# Connector_Board_rev2.net
KiCad netlist of a schematic drawn in EAGLE
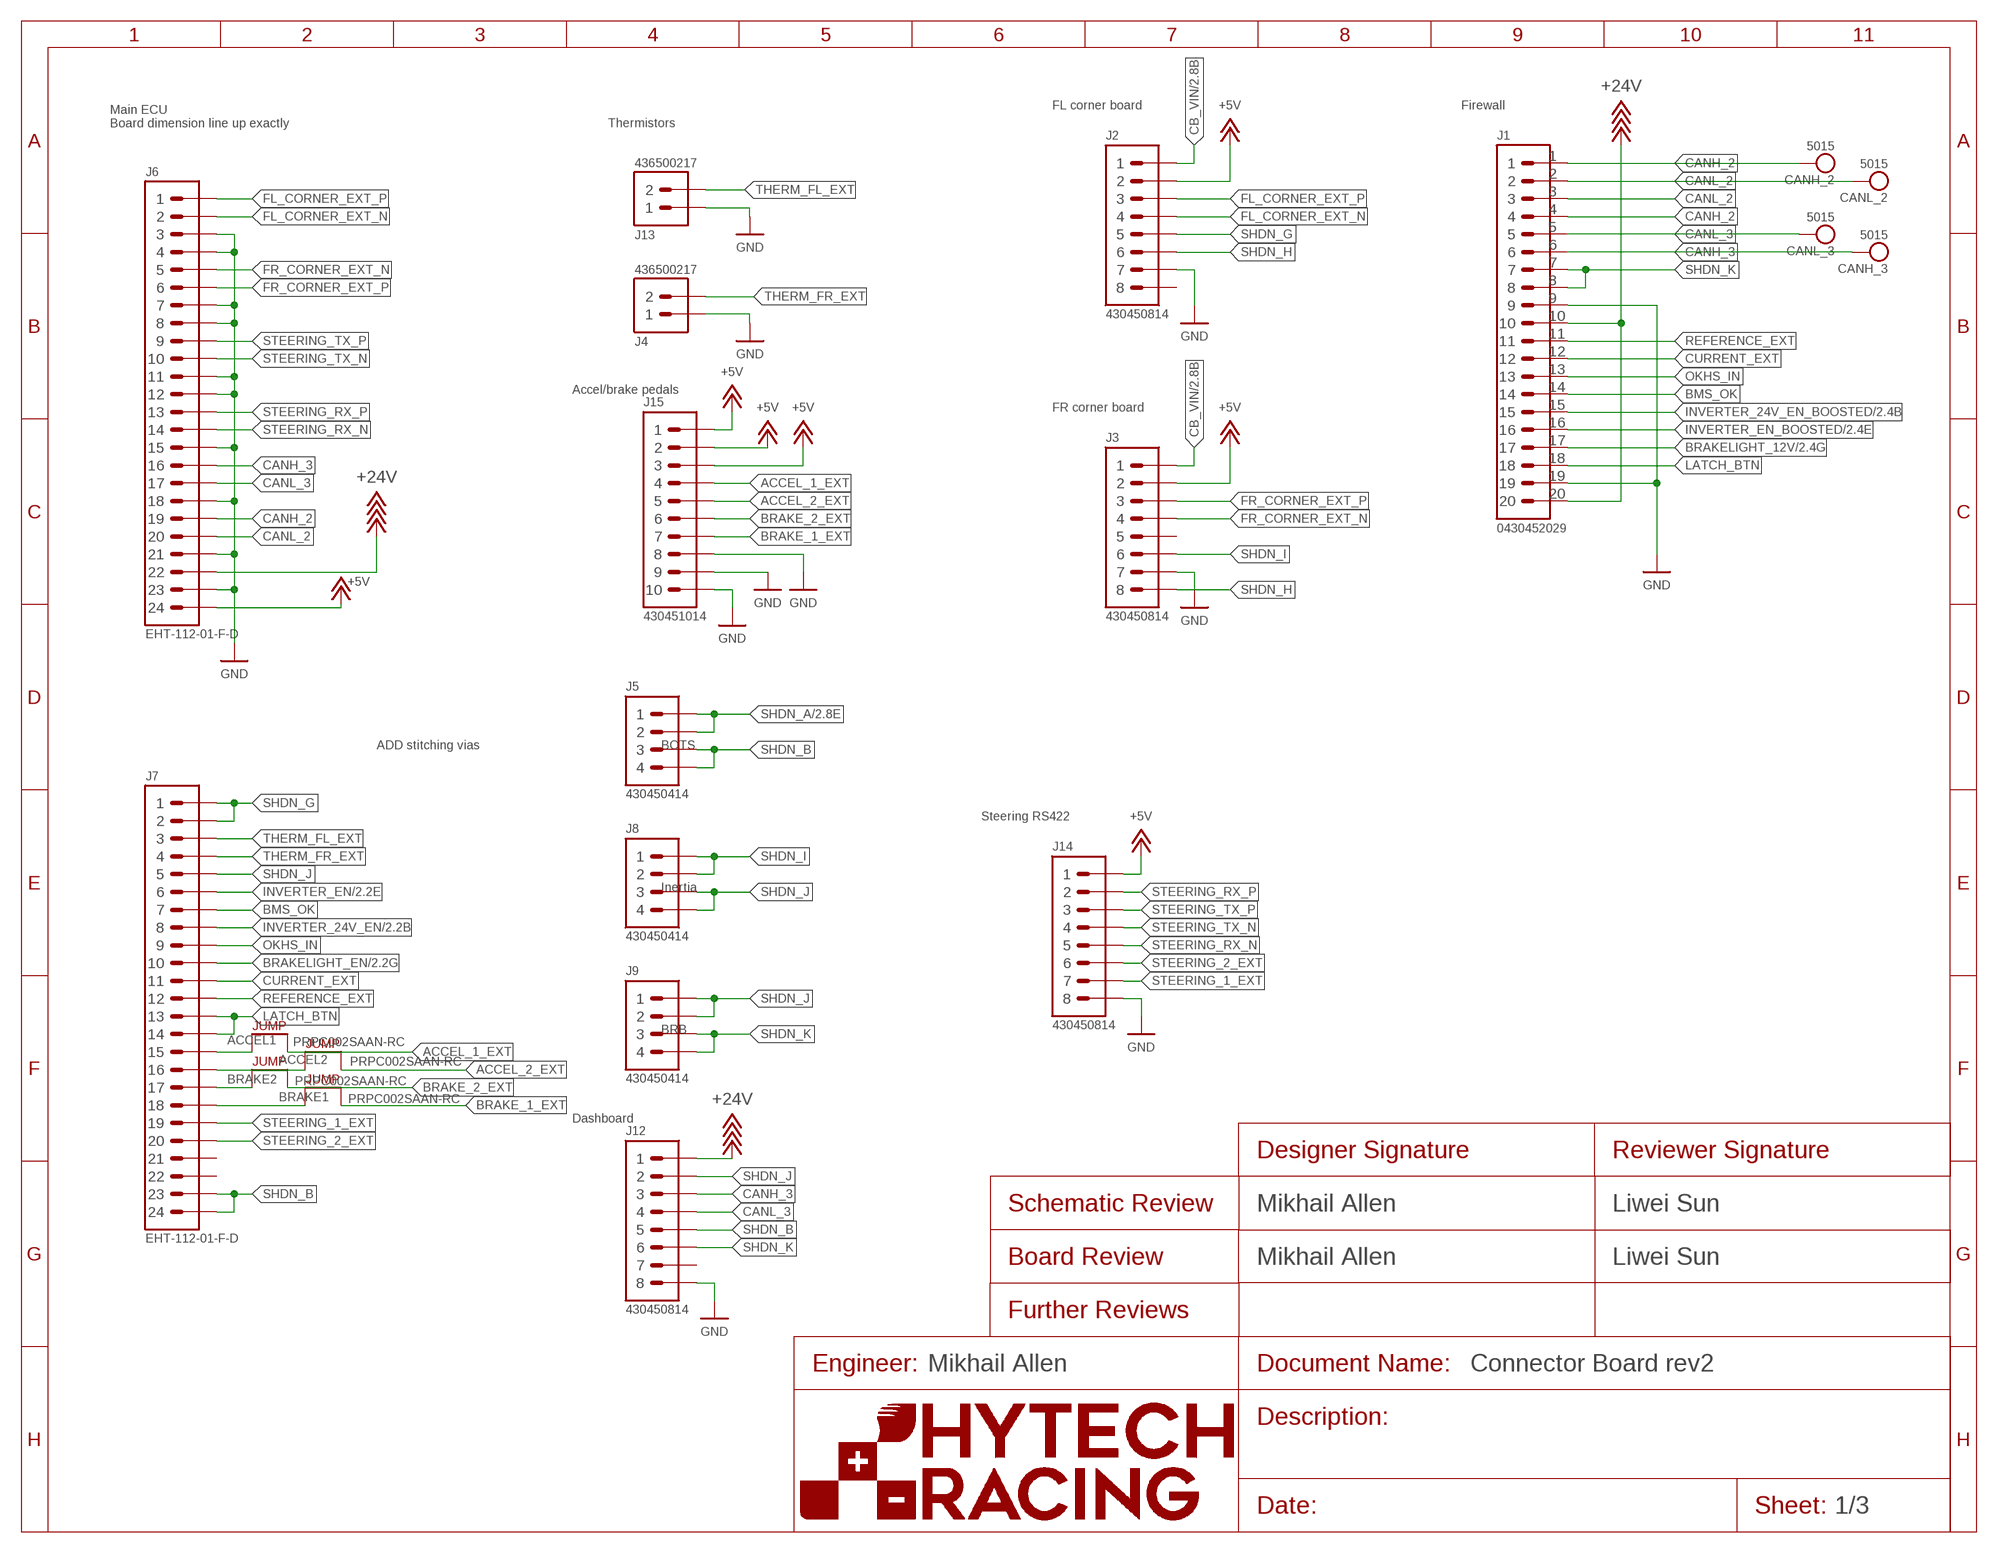
[diagram p0: schematic, sheet 1]
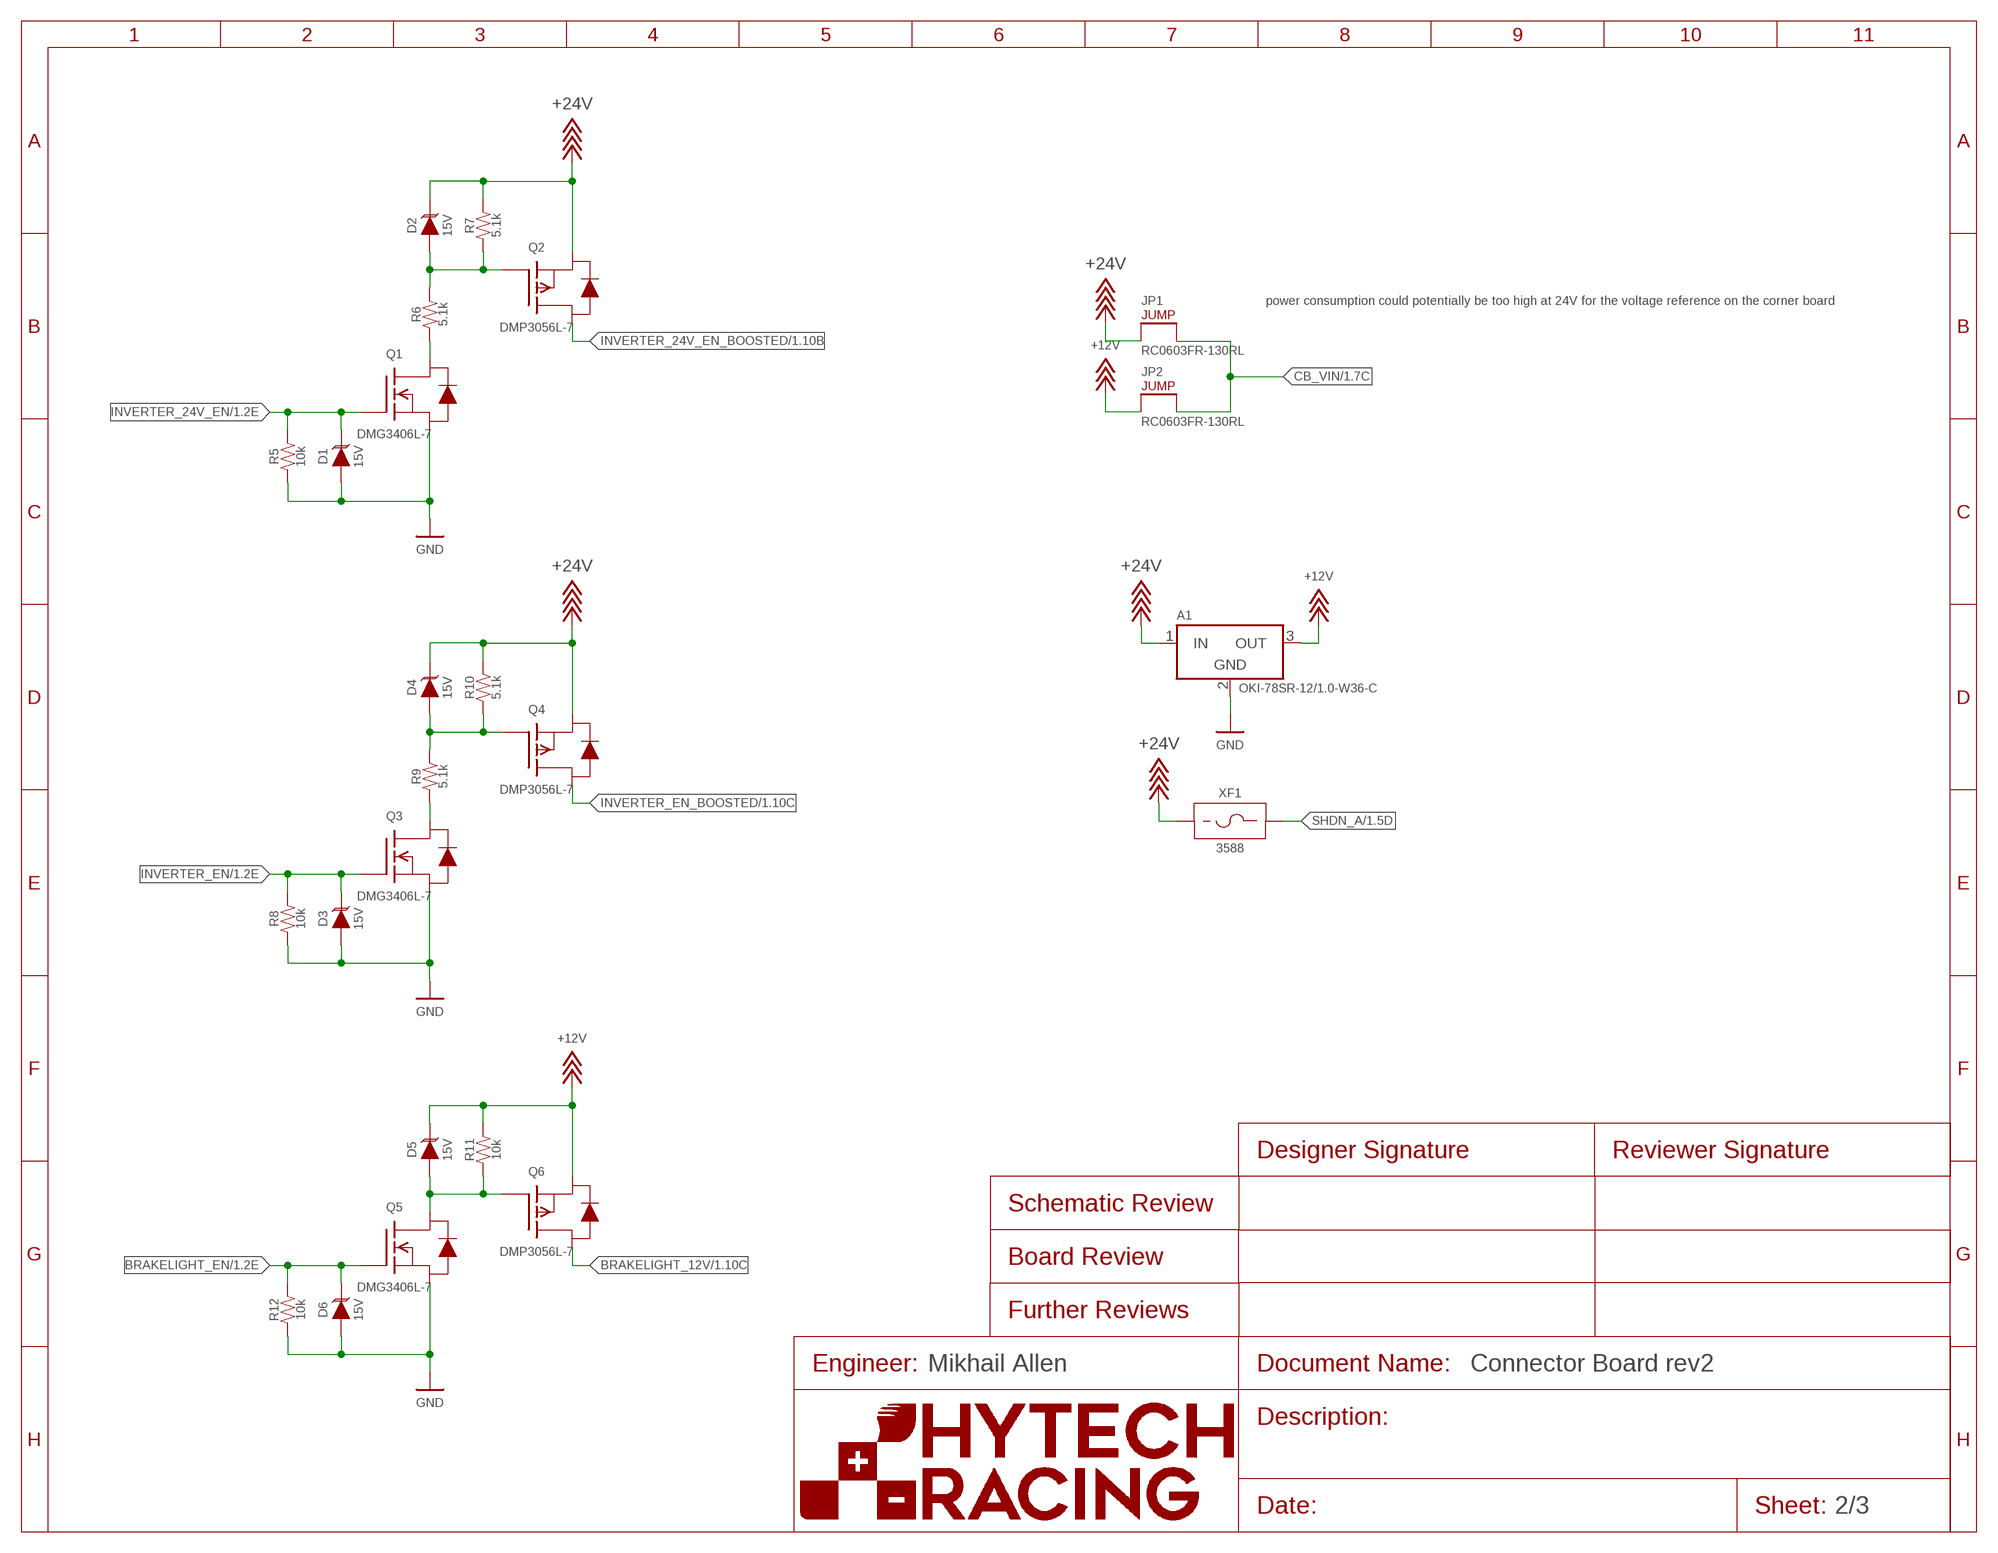
[diagram p1: schematic, sheet 2]
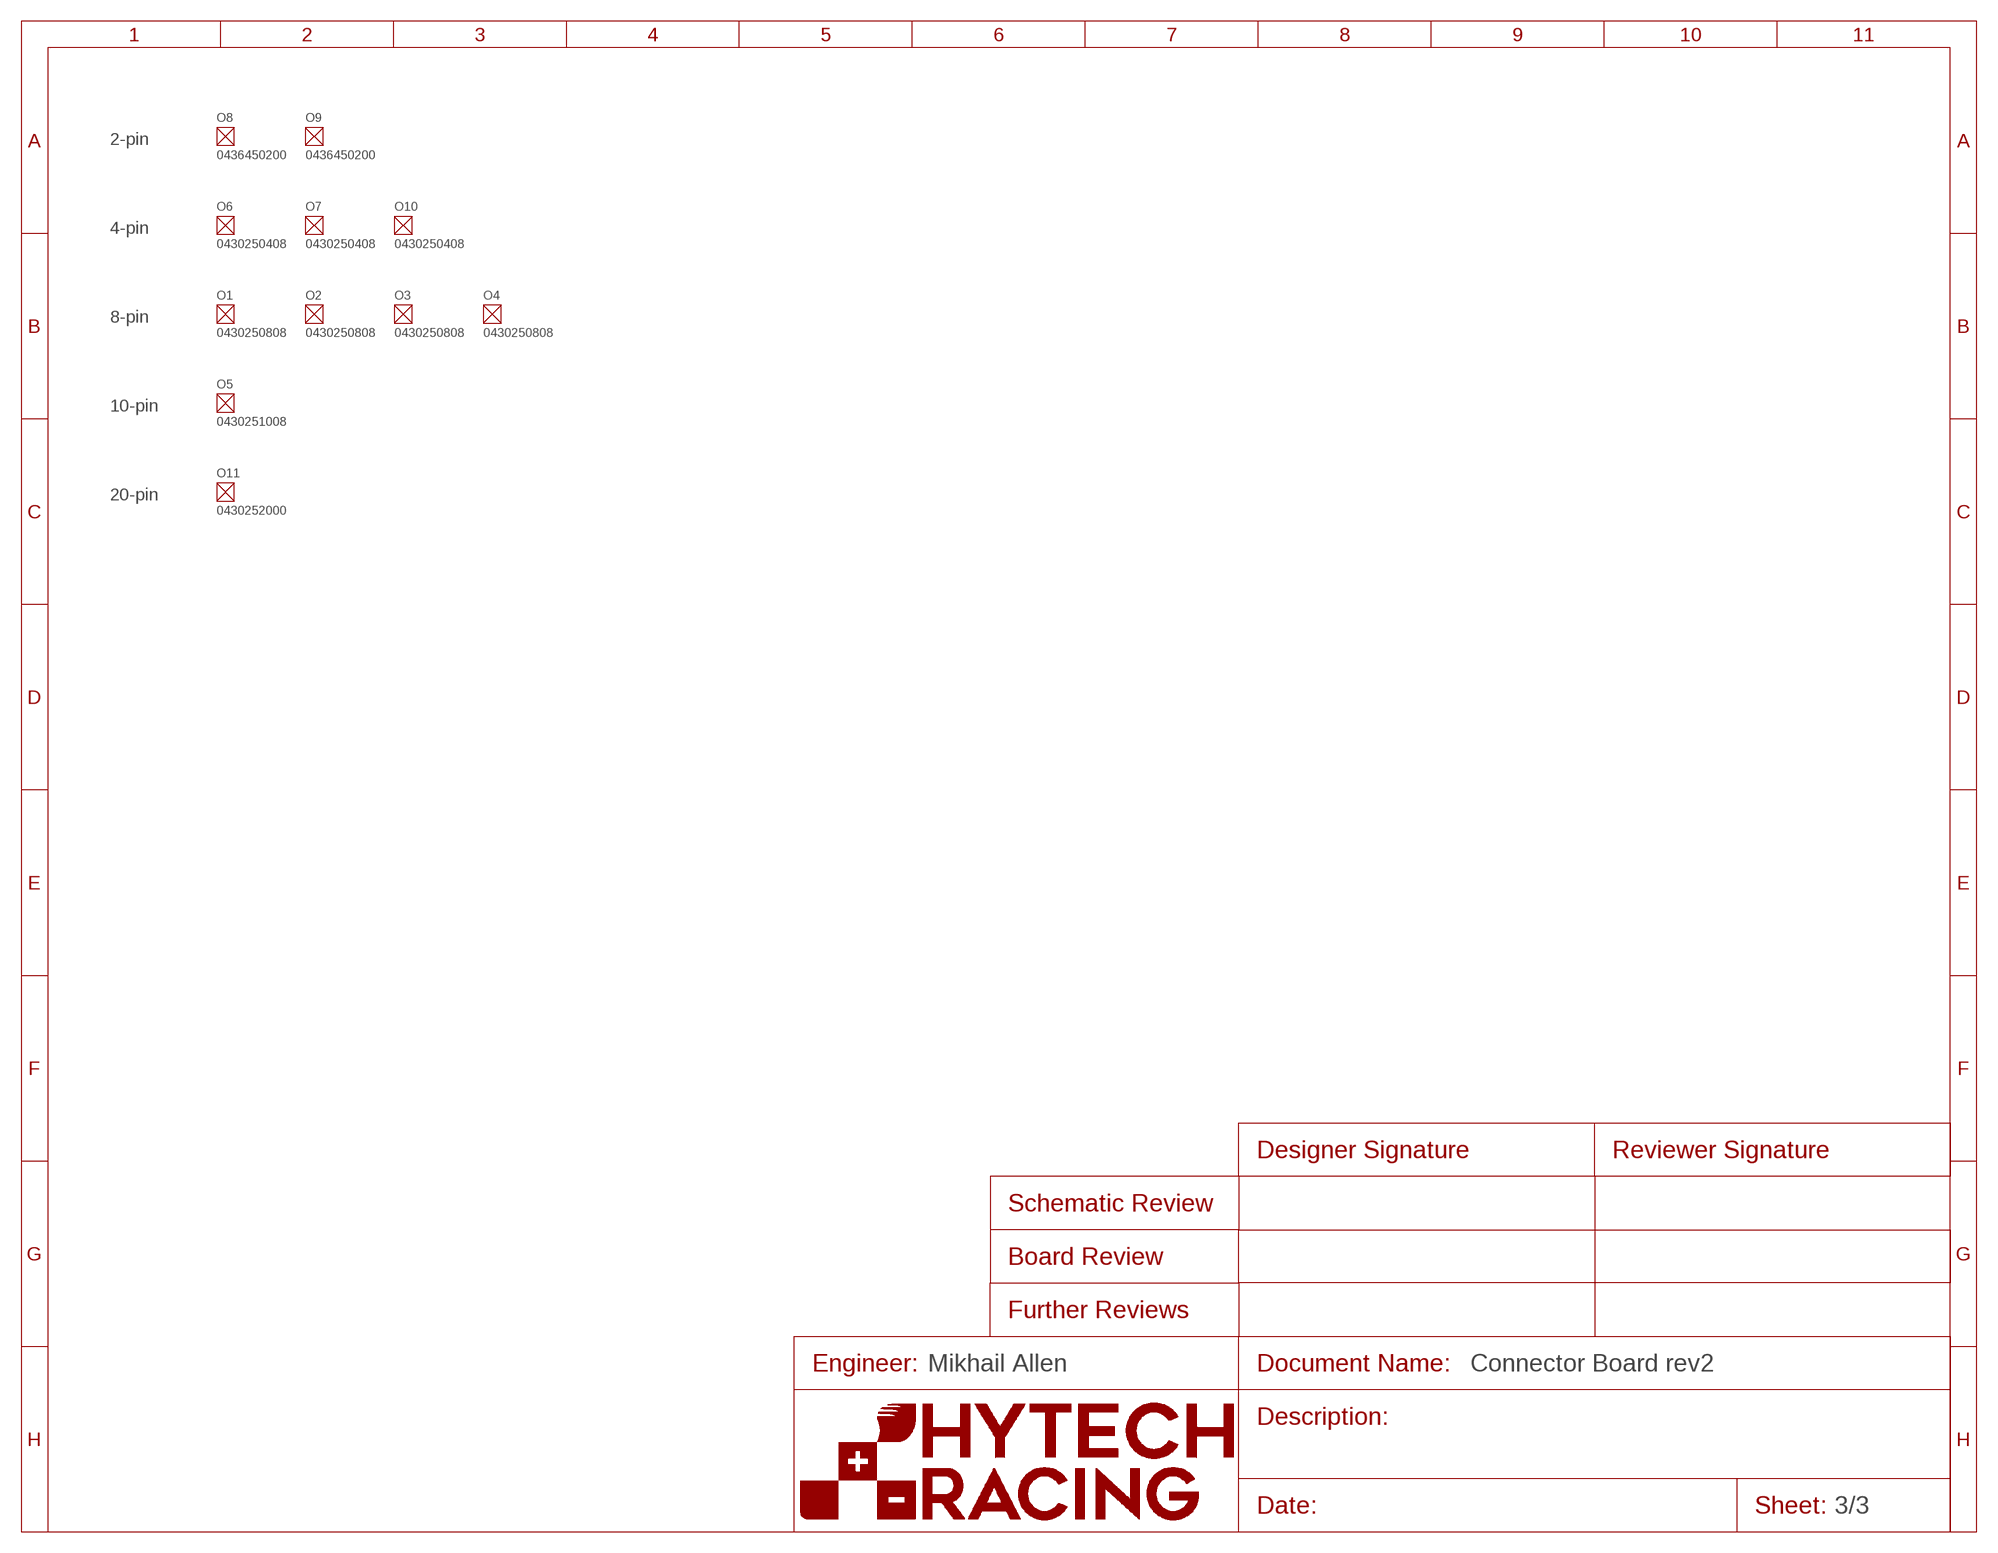
[diagram p2: schematic, sheet 3]

(export (version "E")
  (design (tool "Eeschema 10.0.6"))
  (components
    (comp (ref "ACCEL1")
      (value "JUMPER__1X02")
      (footprint "eagle-import:1X02")
      (fields
        (field (name "MANUFACTURER") "Sullins Connector Solutions")
        (field (name "MPN") "PRPC002SAAN-RC")
      )
      (libsource (lib "eagle-import") (part "JUMPER_?_1X02"))
    )
    (comp (ref "ACCEL2")
      (value "JUMPER__1X02")
      (footprint "eagle-import:1X02")
      (fields
        (field (name "MANUFACTURER") "Sullins Connector Solutions")
        (field (name "MPN") "PRPC002SAAN-RC")
      )
      (libsource (lib "eagle-import") (part "JUMPER_?_1X02"))
    )
    (comp (ref "BRAKE1")
      (value "JUMPER__1X02")
      (footprint "eagle-import:1X02")
      (fields
        (field (name "MANUFACTURER") "Sullins Connector Solutions")
        (field (name "MPN") "PRPC002SAAN-RC")
      )
      (libsource (lib "eagle-import") (part "JUMPER_?_1X02"))
    )
    (comp (ref "BRAKE2")
      (value "JUMPER__1X02")
      (footprint "eagle-import:1X02")
      (fields
        (field (name "MANUFACTURER") "Sullins Connector Solutions")
        (field (name "MPN") "PRPC002SAAN-RC")
      )
      (libsource (lib "eagle-import") (part "JUMPER_?_1X02"))
    )
    (comp (ref "CANH_2")
      (value "TEST_POINT")
      (footprint "eagle-import:5015")
      (fields (field (name "MPN") "5015") (field (name "MANUFACTURER") "Keystone Electronics"))
      (libsource (lib "eagle-import") (part "TEST_POINT"))
    )
    (comp (ref "CANH_3")
      (value "TEST_POINT")
      (footprint "eagle-import:5015")
      (fields (field (name "MPN") "5015") (field (name "MANUFACTURER") "Keystone Electronics"))
      (libsource (lib "eagle-import") (part "TEST_POINT"))
    )
    (comp (ref "CANL_2")
      (value "TEST_POINT")
      (footprint "eagle-import:5015")
      (fields (field (name "MPN") "5015") (field (name "MANUFACTURER") "Keystone Electronics"))
      (libsource (lib "eagle-import") (part "TEST_POINT"))
    )
    (comp (ref "CANL_3")
      (value "TEST_POINT")
      (footprint "eagle-import:5015")
      (fields (field (name "MPN") "5015") (field (name "MANUFACTURER") "Keystone Electronics"))
      (libsource (lib "eagle-import") (part "TEST_POINT"))
    )
    (comp (ref "J1")
      (value "CONNECTOR-20_MF_T_V_")
      (footprint "eagle-import:MOLEX_MICROFIT_PTH_VERTICAL_20_DUAL")
      (fields (field (name "MPN") "0430452029") (field (name "MANUFACTURER") "Molex"))
      (libsource (lib "eagle-import") (part "CONNECTOR-20_?_MF_T_V"))
    )
    (comp (ref "J2")
      (value "CONNECTOR-8_μF_T_V_BLACK")
      (footprint "eagle-import:MOLEX_MICROFIT_PTH_VERTICAL_08_DUAL")
      (fields (field (name "MANUFACTURER") "Molex") (field (name "MPN") "430450814"))
      (libsource (lib "eagle-import") (part "CONNECTOR-8_?_μF_T_VBLACK"))
    )
    (comp (ref "J3")
      (value "CONNECTOR-8_μF_T_V_BLACK")
      (footprint "eagle-import:MOLEX_MICROFIT_PTH_VERTICAL_08_DUAL")
      (fields (field (name "MANUFACTURER") "Molex") (field (name "MPN") "430450814"))
      (libsource (lib "eagle-import") (part "CONNECTOR-8_?_μF_T_VBLACK"))
    )
    (comp (ref "J4")
      (value "CONNECTOR-2_MF_T_V_")
      (footprint "eagle-import:MOLEX_MICROFIT_PTH_VERTICAL_02_SINGLE")
      (fields (field (name "MPN") "436500217") (field (name "MANUFACTURER") "MOLEX"))
      (libsource (lib "eagle-import") (part "CONNECTOR-2_?_MF_T_V"))
    )
    (comp (ref "J5")
      (value "CONNECTOR-4_μF_T_V_BLACK")
      (footprint "eagle-import:MOLEX_MICROFIT_PTH_VERTICAL_04_DUAL")
      (fields (field (name "MANUFACTURER") "Molex") (field (name "MPN") "430450414"))
      (libsource (lib "eagle-import") (part "CONNECTOR-4_?_μF_T_VBLACK"))
    )
    (comp (ref "J6")
      (value "CONNECTOR-24_CONNECTOR-24_")
      (footprint "eagle-import:EHT-112-01")
      (fields (field (name "MPN") "EHT-112-01-F-D") (field (name "MANUFACTURER") "Samtec"))
      (libsource (lib "eagle-import") (part "CONNECTOR-24_?_CONNECTOR-24"))
    )
    (comp (ref "J7")
      (value "CONNECTOR-24_CONNECTOR-24_")
      (footprint "eagle-import:EHT-112-01")
      (fields (field (name "MPN") "EHT-112-01-F-D") (field (name "MANUFACTURER") "Samtec"))
      (libsource (lib "eagle-import") (part "CONNECTOR-24_?_CONNECTOR-24"))
    )
    (comp (ref "J8")
      (value "CONNECTOR-4_μF_T_V_BLACK")
      (footprint "eagle-import:MOLEX_MICROFIT_PTH_VERTICAL_04_DUAL")
      (fields (field (name "MANUFACTURER") "Molex") (field (name "MPN") "430450414"))
      (libsource (lib "eagle-import") (part "CONNECTOR-4_?_μF_T_VBLACK"))
    )
    (comp (ref "J9")
      (value "CONNECTOR-4_μF_T_V_BLACK")
      (footprint "eagle-import:MOLEX_MICROFIT_PTH_VERTICAL_04_DUAL")
      (fields (field (name "MANUFACTURER") "Molex") (field (name "MPN") "430450414"))
      (libsource (lib "eagle-import") (part "CONNECTOR-4_?_μF_T_VBLACK"))
    )
    (comp (ref "J12")
      (value "CONNECTOR-8_μF_T_V_BLACK")
      (footprint "eagle-import:MOLEX_MICROFIT_PTH_VERTICAL_08_DUAL")
      (fields (field (name "MANUFACTURER") "Molex") (field (name "MPN") "430450814"))
      (libsource (lib "eagle-import") (part "CONNECTOR-8_?_μF_T_VBLACK"))
    )
    (comp (ref "J13")
      (value "CONNECTOR-2_MF_T_V_")
      (footprint "eagle-import:MOLEX_MICROFIT_PTH_VERTICAL_02_SINGLE")
      (fields (field (name "MPN") "436500217") (field (name "MANUFACTURER") "MOLEX"))
      (libsource (lib "eagle-import") (part "CONNECTOR-2_?_MF_T_V"))
    )
    (comp (ref "J14")
      (value "CONNECTOR-8_μF_T_V_BLACK")
      (footprint "eagle-import:MOLEX_MICROFIT_PTH_VERTICAL_08_DUAL")
      (fields (field (name "MANUFACTURER") "Molex") (field (name "MPN") "430450814"))
      (libsource (lib "eagle-import") (part "CONNECTOR-8_?_μF_T_VBLACK"))
    )
    (comp (ref "J15")
      (value "CONNECTOR-10_MF_T_V_")
      (footprint "eagle-import:MOLEX_MICROFIT_PTH_VERTICAL_10_DUAL")
      (fields (field (name "MPN") "430451014") (field (name "MANUFACTURER") "MOLEX"))
      (libsource (lib "eagle-import") (part "CONNECTOR-10_?_MF_T_V"))
    )
    (comp (ref "A1")
      (value "VOLTAGE_REGULATOR_MODULE_OKI-78SR_12V")
      (footprint "eagle-import:OKI-78SR")
      (fields
        (field (name "MANUFACTURER") "Murata Power Solutions Inc.")
        (field (name "MPN") "OKI-78SR-12/1.0-W36-C")
      )
      (libsource (lib "eagle-import") (part "VOLTAGE_REGULATOR_MODULE_?_OKI-78SR12V"))
    )
    (comp (ref "D1")
      (value "TVS__15V")
      (footprint "eagle-import:SOT-23")
      (fields
        (field (name "MANUFACTURER") "Vishay General Semiconductor - Diodes Division")
        (field (name "MPN") "GSOT15-E3-08")
        (field (name "VOLTAGE") "15V")
      )
      (libsource (lib "eagle-import") (part "TVS_?_15V"))
    )
    (comp (ref "D2")
      (value "TVS__15V")
      (footprint "eagle-import:SOT-23")
      (fields
        (field (name "MANUFACTURER") "Vishay General Semiconductor - Diodes Division")
        (field (name "MPN") "GSOT15-E3-08")
        (field (name "VOLTAGE") "15V")
      )
      (libsource (lib "eagle-import") (part "TVS_?_15V"))
    )
    (comp (ref "D3")
      (value "TVS__15V")
      (footprint "eagle-import:SOT-23")
      (fields
        (field (name "MANUFACTURER") "Vishay General Semiconductor - Diodes Division")
        (field (name "MPN") "GSOT15-E3-08")
        (field (name "VOLTAGE") "15V")
      )
      (libsource (lib "eagle-import") (part "TVS_?_15V"))
    )
    (comp (ref "D4")
      (value "TVS__15V")
      (footprint "eagle-import:SOT-23")
      (fields
        (field (name "MANUFACTURER") "Vishay General Semiconductor - Diodes Division")
        (field (name "MPN") "GSOT15-E3-08")
        (field (name "VOLTAGE") "15V")
      )
      (libsource (lib "eagle-import") (part "TVS_?_15V"))
    )
    (comp (ref "D5")
      (value "TVS__15V")
      (footprint "eagle-import:SOT-23")
      (fields
        (field (name "MANUFACTURER") "Vishay General Semiconductor - Diodes Division")
        (field (name "MPN") "GSOT15-E3-08")
        (field (name "VOLTAGE") "15V")
      )
      (libsource (lib "eagle-import") (part "TVS_?_15V"))
    )
    (comp (ref "D6")
      (value "TVS__15V")
      (footprint "eagle-import:SOT-23")
      (fields
        (field (name "MANUFACTURER") "Vishay General Semiconductor - Diodes Division")
        (field (name "MPN") "GSOT15-E3-08")
        (field (name "VOLTAGE") "15V")
      )
      (libsource (lib "eagle-import") (part "TVS_?_15V"))
    )
    (comp (ref "JP1")
      (value "JUMPER_0603_")
      (footprint "eagle-import:0603-RES")
      (fields (field (name "MPN") "RC0603FR-130RL") (field (name "MANUFACTURER") "YAGEO"))
      (libsource (lib "eagle-import") (part "JUMPER_?_0603"))
    )
    (comp (ref "JP2")
      (value "JUMPER_0603_")
      (footprint "eagle-import:0603-RES")
      (fields (field (name "MPN") "RC0603FR-130RL") (field (name "MANUFACTURER") "YAGEO"))
      (libsource (lib "eagle-import") (part "JUMPER_?_0603"))
    )
    (comp (ref "Q1")
      (value "TRANSISTOR_N_MOS__DMG3406L-7")
      (footprint "eagle-import:SOT-23")
      (fields (field (name "MANUFACTURER") "Diodes Incorporated") (field (name "MPN") "DMG3406L-7"))
      (libsource (lib "eagle-import") (part "TRANSISTOR_N_MOS_?_DMG3406L-7"))
    )
    (comp (ref "Q2")
      (value "TRANSISTOR_P_MOS_SOT-23_DMP3056L-7")
      (footprint "eagle-import:SOT-23")
      (fields (field (name "MANUFACTURER") "Diodes Incorporated") (field (name "MPN") "DMP3056L-7"))
      (libsource (lib "eagle-import") (part "TRANSISTOR_P_MOS_?_SOT-23DMP3056L-7"))
    )
    (comp (ref "Q3")
      (value "TRANSISTOR_N_MOS__DMG3406L-7")
      (footprint "eagle-import:SOT-23")
      (fields (field (name "MANUFACTURER") "Diodes Incorporated") (field (name "MPN") "DMG3406L-7"))
      (libsource (lib "eagle-import") (part "TRANSISTOR_N_MOS_?_DMG3406L-7"))
    )
    (comp (ref "Q4")
      (value "TRANSISTOR_P_MOS_SOT-23_DMP3056L-7")
      (footprint "eagle-import:SOT-23")
      (fields (field (name "MANUFACTURER") "Diodes Incorporated") (field (name "MPN") "DMP3056L-7"))
      (libsource (lib "eagle-import") (part "TRANSISTOR_P_MOS_?_SOT-23DMP3056L-7"))
    )
    (comp (ref "Q5")
      (value "TRANSISTOR_N_MOS__DMG3406L-7")
      (footprint "eagle-import:SOT-23")
      (fields (field (name "MANUFACTURER") "Diodes Incorporated") (field (name "MPN") "DMG3406L-7"))
      (libsource (lib "eagle-import") (part "TRANSISTOR_N_MOS_?_DMG3406L-7"))
    )
    (comp (ref "Q6")
      (value "TRANSISTOR_P_MOS_SOT-23_DMP3056L-7")
      (footprint "eagle-import:SOT-23")
      (fields (field (name "MANUFACTURER") "Diodes Incorporated") (field (name "MPN") "DMP3056L-7"))
      (libsource (lib "eagle-import") (part "TRANSISTOR_P_MOS_?_SOT-23DMP3056L-7"))
    )
    (comp (ref "R5")
      (value "RESISTOR_0603_10K")
      (footprint "eagle-import:0603-RES")
      (fields
        (field (name "MANUFACTURER") "Panasonic Electronic Components")
        (field (name "MPN") "ERA-3ARB103V")
        (field (name "POWER") "0.1W")
        (field (name "RESISTANCE") "10k")
      )
      (libsource (lib "eagle-import") (part "RESISTOR_?_060310K"))
    )
    (comp (ref "R6")
      (value "RESISTOR_0603_5.1K")
      (footprint "eagle-import:0603-RES")
      (fields
        (field (name "MANUFACTURER") "Yageo")
        (field (name "MPN") "RC0603FR-075K1L")
        (field (name "POWER") "0.1W")
        (field (name "RESISTANCE") "5.1k")
      )
      (libsource (lib "eagle-import") (part "RESISTOR_?_06035.1K"))
    )
    (comp (ref "R7")
      (value "RESISTOR_0603_5.1K")
      (footprint "eagle-import:0603-RES")
      (fields
        (field (name "MANUFACTURER") "Yageo")
        (field (name "MPN") "RC0603FR-075K1L")
        (field (name "POWER") "0.1W")
        (field (name "RESISTANCE") "5.1k")
      )
      (libsource (lib "eagle-import") (part "RESISTOR_?_06035.1K"))
    )
    (comp (ref "R8")
      (value "RESISTOR_0603_10K")
      (footprint "eagle-import:0603-RES")
      (fields
        (field (name "MANUFACTURER") "Panasonic Electronic Components")
        (field (name "MPN") "ERA-3ARB103V")
        (field (name "POWER") "0.1W")
        (field (name "RESISTANCE") "10k")
      )
      (libsource (lib "eagle-import") (part "RESISTOR_?_060310K"))
    )
    (comp (ref "R9")
      (value "RESISTOR_0603_5.1K")
      (footprint "eagle-import:0603-RES")
      (fields
        (field (name "MANUFACTURER") "Yageo")
        (field (name "MPN") "RC0603FR-075K1L")
        (field (name "POWER") "0.1W")
        (field (name "RESISTANCE") "5.1k")
      )
      (libsource (lib "eagle-import") (part "RESISTOR_?_06035.1K"))
    )
    (comp (ref "R10")
      (value "RESISTOR_0603_5.1K")
      (footprint "eagle-import:0603-RES")
      (fields
        (field (name "MANUFACTURER") "Yageo")
        (field (name "MPN") "RC0603FR-075K1L")
        (field (name "POWER") "0.1W")
        (field (name "RESISTANCE") "5.1k")
      )
      (libsource (lib "eagle-import") (part "RESISTOR_?_06035.1K"))
    )
    (comp (ref "R11")
      (value "RESISTOR_0603_10K")
      (footprint "eagle-import:0603-RES")
      (fields
        (field (name "MANUFACTURER") "Panasonic Electronic Components")
        (field (name "MPN") "ERA-3ARB103V")
        (field (name "POWER") "0.1W")
        (field (name "RESISTANCE") "10k")
      )
      (libsource (lib "eagle-import") (part "RESISTOR_?_060310K"))
    )
    (comp (ref "R12")
      (value "RESISTOR_0603_10K")
      (footprint "eagle-import:0603-RES")
      (fields
        (field (name "MANUFACTURER") "Panasonic Electronic Components")
        (field (name "MPN") "ERA-3ARB103V")
        (field (name "POWER") "0.1W")
        (field (name "RESISTANCE") "10k")
      )
      (libsource (lib "eagle-import") (part "RESISTOR_?_060310K"))
    )
    (comp (ref "XF1")
      (value "FUSE_HOLDER_MINIBLADESMD")
      (footprint "eagle-import:3588")
      (fields (field (name "MANUFACTURER") "Keystone Electronics") (field (name "MPN") "3588"))
      (libsource (lib "eagle-import") (part "FUSE_HOLDER_SMDMINIBLADE"))
    )
  )
  (nets
    (net (code "1") (name "+5V") (class "Default")
      (node (ref "J14") (pin "1") (pinfunction "1_1") (pintype "passive"))
      (node (ref "J15") (pin "1") (pinfunction "1_1") (pintype "passive"))
      (node (ref "J15") (pin "2") (pinfunction "2_2") (pintype "passive"))
      (node (ref "J15") (pin "3") (pinfunction "3_3") (pintype "passive"))
      (node (ref "J2") (pin "2") (pinfunction "2_2") (pintype "passive"))
      (node (ref "J3") (pin "2") (pinfunction "2_2") (pintype "passive"))
      (node (ref "J6") (pin "24") (pinfunction "24_24") (pintype "passive"))
    )
    (net (code "2") (name "+12V") (class "Default")
      (node (ref "A1") (pin "3") (pinfunction "OUT_3") (pintype "power_in"))
      (node (ref "D5") (pin "3") (pinfunction "C_3") (pintype "passive"))
      (node (ref "JP2") (pin "1") (pinfunction "1_1") (pintype "passive"))
      (node (ref "Q6") (pin "2") (pinfunction "S_2") (pintype "passive"))
      (node (ref "R11") (pin "2") (pinfunction "2_2") (pintype "passive"))
    )
    (net (code "3") (name "+24V") (class "Default")
      (node (ref "A1") (pin "1") (pinfunction "IN_1") (pintype "power_in"))
      (node (ref "D2") (pin "3") (pinfunction "C_3") (pintype "passive"))
      (node (ref "D4") (pin "3") (pinfunction "C_3") (pintype "passive"))
      (node (ref "J1") (pin "10") (pinfunction "10_10") (pintype "passive"))
      (node (ref "J1") (pin "20") (pinfunction "20_20") (pintype "passive"))
      (node (ref "J12") (pin "1") (pinfunction "1_1") (pintype "passive"))
      (node (ref "J6") (pin "22") (pinfunction "22_22") (pintype "passive"))
      (node (ref "JP1") (pin "1") (pinfunction "1_1") (pintype "passive"))
      (node (ref "Q2") (pin "2") (pinfunction "S_2") (pintype "passive"))
      (node (ref "Q4") (pin "2") (pinfunction "S_2") (pintype "passive"))
      (node (ref "R10") (pin "2") (pinfunction "2_2") (pintype "passive"))
      (node (ref "R7") (pin "2") (pinfunction "2_2") (pintype "passive"))
      (node (ref "XF1") (pin "1") (pinfunction "1_1") (pintype "passive"))
      (node (ref "XF1") (pin "2") (pinfunction "1_2") (pintype "passive"))
    )
    (net (code "4") (name "ACCEL_1_EXT") (class "Default")
      (node (ref "ACCEL1") (pin "2") (pinfunction "2_2") (pintype "passive"))
      (node (ref "J15") (pin "4") (pinfunction "4_4") (pintype "passive"))
    )
    (net (code "5") (name "ACCEL_2_EXT") (class "Default")
      (node (ref "ACCEL2") (pin "2") (pinfunction "2_2") (pintype "passive"))
      (node (ref "J15") (pin "5") (pinfunction "5_5") (pintype "passive"))
    )
    (net (code "6") (name "BMS_OK") (class "Default")
      (node (ref "J1") (pin "14") (pinfunction "14_14") (pintype "passive"))
      (node (ref "J7") (pin "7") (pinfunction "7_7") (pintype "passive"))
    )
    (net (code "7") (name "BRAKELIGHT_12V") (class "Default")
      (node (ref "J1") (pin "17") (pinfunction "17_17") (pintype "passive"))
      (node (ref "Q6") (pin "3") (pinfunction "D_3") (pintype "passive"))
    )
    (net (code "8") (name "BRAKELIGHT_EN") (class "Default")
      (node (ref "D6") (pin "3") (pinfunction "C_3") (pintype "passive"))
      (node (ref "J7") (pin "10") (pinfunction "10_10") (pintype "passive"))
      (node (ref "Q5") (pin "1") (pinfunction "G_1") (pintype "passive"))
      (node (ref "R12") (pin "2") (pinfunction "2_2") (pintype "passive"))
    )
    (net (code "9") (name "BRAKE_1_EXT") (class "Default")
      (node (ref "BRAKE1") (pin "2") (pinfunction "2_2") (pintype "passive"))
      (node (ref "J15") (pin "7") (pinfunction "7_7") (pintype "passive"))
    )
    (net (code "10") (name "BRAKE_2_EXT") (class "Default")
      (node (ref "BRAKE2") (pin "2") (pinfunction "2_2") (pintype "passive"))
      (node (ref "J15") (pin "6") (pinfunction "6_6") (pintype "passive"))
    )
    (net (code "11") (name "CANH_2") (class "Default")
      (node (ref "CANH_2") (pin "1") (pinfunction "1_1") (pintype "passive"))
      (node (ref "J1") (pin "1") (pinfunction "1_1") (pintype "passive"))
      (node (ref "J1") (pin "4") (pinfunction "4_4") (pintype "passive"))
      (node (ref "J6") (pin "19") (pinfunction "19_19") (pintype "passive"))
    )
    (net (code "12") (name "CANH_3") (class "Default")
      (node (ref "CANH_3") (pin "1") (pinfunction "1_1") (pintype "passive"))
      (node (ref "J1") (pin "6") (pinfunction "6_6") (pintype "passive"))
      (node (ref "J12") (pin "3") (pinfunction "3_3") (pintype "passive"))
      (node (ref "J6") (pin "16") (pinfunction "16_16") (pintype "passive"))
    )
    (net (code "13") (name "CANL_2") (class "Default")
      (node (ref "CANL_2") (pin "1") (pinfunction "1_1") (pintype "passive"))
      (node (ref "J1") (pin "2") (pinfunction "2_2") (pintype "passive"))
      (node (ref "J1") (pin "3") (pinfunction "3_3") (pintype "passive"))
      (node (ref "J6") (pin "20") (pinfunction "20_20") (pintype "passive"))
    )
    (net (code "14") (name "CANL_3") (class "Default")
      (node (ref "CANL_3") (pin "1") (pinfunction "1_1") (pintype "passive"))
      (node (ref "J1") (pin "5") (pinfunction "5_5") (pintype "passive"))
      (node (ref "J12") (pin "4") (pinfunction "4_4") (pintype "passive"))
      (node (ref "J6") (pin "17") (pinfunction "17_17") (pintype "passive"))
    )
    (net (code "15") (name "CB_VIN") (class "Default")
      (node (ref "J2") (pin "1") (pinfunction "1_1") (pintype "passive"))
      (node (ref "J3") (pin "1") (pinfunction "1_1") (pintype "passive"))
      (node (ref "JP1") (pin "2") (pinfunction "2_2") (pintype "passive"))
      (node (ref "JP2") (pin "2") (pinfunction "2_2") (pintype "passive"))
    )
    (net (code "16") (name "CURRENT_EXT") (class "Default")
      (node (ref "J1") (pin "12") (pinfunction "12_12") (pintype "passive"))
      (node (ref "J7") (pin "11") (pinfunction "11_11") (pintype "passive"))
    )
    (net (code "17") (name "FL_CORNER_EXT_N") (class "Default")
      (node (ref "J2") (pin "4") (pinfunction "4_4") (pintype "passive"))
      (node (ref "J6") (pin "2") (pinfunction "2_2") (pintype "passive"))
    )
    (net (code "18") (name "FL_CORNER_EXT_P") (class "Default")
      (node (ref "J2") (pin "3") (pinfunction "3_3") (pintype "passive"))
      (node (ref "J6") (pin "1") (pinfunction "1_1") (pintype "passive"))
    )
    (net (code "19") (name "FR_CORNER_EXT_N") (class "Default")
      (node (ref "J3") (pin "4") (pinfunction "4_4") (pintype "passive"))
      (node (ref "J6") (pin "5") (pinfunction "5_5") (pintype "passive"))
    )
    (net (code "20") (name "FR_CORNER_EXT_P") (class "Default")
      (node (ref "J3") (pin "3") (pinfunction "3_3") (pintype "passive"))
      (node (ref "J6") (pin "6") (pinfunction "6_6") (pintype "passive"))
    )
    (net (code "21") (name "GND") (class "Default")
      (node (ref "A1") (pin "2") (pinfunction "GND_2") (pintype "power_in"))
      (node (ref "D1") (pin "1") (pinfunction "A_1") (pintype "passive"))
      (node (ref "D3") (pin "1") (pinfunction "A_1") (pintype "passive"))
      (node (ref "D6") (pin "1") (pinfunction "A_1") (pintype "passive"))
      (node (ref "J1") (pin "19") (pinfunction "19_19") (pintype "passive"))
      (node (ref "J1") (pin "9") (pinfunction "9_9") (pintype "passive"))
      (node (ref "J12") (pin "8") (pinfunction "8_8") (pintype "passive"))
      (node (ref "J13") (pin "1") (pinfunction "1_1") (pintype "passive"))
      (node (ref "J14") (pin "8") (pinfunction "8_8") (pintype "passive"))
      (node (ref "J15") (pin "10") (pinfunction "10_10") (pintype "passive"))
      (node (ref "J15") (pin "8") (pinfunction "8_8") (pintype "passive"))
      (node (ref "J15") (pin "9") (pinfunction "9_9") (pintype "passive"))
      (node (ref "J2") (pin "7") (pinfunction "7_7") (pintype "passive"))
      (node (ref "J3") (pin "7") (pinfunction "7_7") (pintype "passive"))
      (node (ref "J4") (pin "1") (pinfunction "1_1") (pintype "passive"))
      (node (ref "J6") (pin "11") (pinfunction "11_11") (pintype "passive"))
      (node (ref "J6") (pin "12") (pinfunction "12_12") (pintype "passive"))
      (node (ref "J6") (pin "15") (pinfunction "15_15") (pintype "passive"))
      (node (ref "J6") (pin "18") (pinfunction "18_18") (pintype "passive"))
      (node (ref "J6") (pin "21") (pinfunction "21_21") (pintype "passive"))
      (node (ref "J6") (pin "23") (pinfunction "23_23") (pintype "passive"))
      (node (ref "J6") (pin "3") (pinfunction "3_3") (pintype "passive"))
      (node (ref "J6") (pin "4") (pinfunction "4_4") (pintype "passive"))
      (node (ref "J6") (pin "7") (pinfunction "7_7") (pintype "passive"))
      (node (ref "J6") (pin "8") (pinfunction "8_8") (pintype "passive"))
      (node (ref "Q1") (pin "2") (pinfunction "S_2") (pintype "passive"))
      (node (ref "Q3") (pin "2") (pinfunction "S_2") (pintype "passive"))
      (node (ref "Q5") (pin "2") (pinfunction "S_2") (pintype "passive"))
      (node (ref "R12") (pin "1") (pinfunction "1_1") (pintype "passive"))
      (node (ref "R5") (pin "1") (pinfunction "1_1") (pintype "passive"))
      (node (ref "R8") (pin "1") (pinfunction "1_1") (pintype "passive"))
    )
    (net (code "22") (name "INVERTER_24V_EN") (class "Default")
      (node (ref "D1") (pin "3") (pinfunction "C_3") (pintype "passive"))
      (node (ref "J7") (pin "8") (pinfunction "8_8") (pintype "passive"))
      (node (ref "Q1") (pin "1") (pinfunction "G_1") (pintype "passive"))
      (node (ref "R5") (pin "2") (pinfunction "2_2") (pintype "passive"))
    )
    (net (code "23") (name "INVERTER_24V_EN_BOOSTED") (class "Default")
      (node (ref "J1") (pin "15") (pinfunction "15_15") (pintype "passive"))
      (node (ref "Q2") (pin "3") (pinfunction "D_3") (pintype "passive"))
    )
    (net (code "24") (name "INVERTER_EN") (class "Default")
      (node (ref "D3") (pin "3") (pinfunction "C_3") (pintype "passive"))
      (node (ref "J7") (pin "6") (pinfunction "6_6") (pintype "passive"))
      (node (ref "Q3") (pin "1") (pinfunction "G_1") (pintype "passive"))
      (node (ref "R8") (pin "2") (pinfunction "2_2") (pintype "passive"))
    )
    (net (code "25") (name "INVERTER_EN_BOOSTED") (class "Default")
      (node (ref "J1") (pin "16") (pinfunction "16_16") (pintype "passive"))
      (node (ref "Q4") (pin "3") (pinfunction "D_3") (pintype "passive"))
    )
    (net (code "26") (name "LATCH_BTN") (class "Default")
      (node (ref "J1") (pin "18") (pinfunction "18_18") (pintype "passive"))
      (node (ref "J7") (pin "13") (pinfunction "13_13") (pintype "passive"))
      (node (ref "J7") (pin "14") (pinfunction "14_14") (pintype "passive"))
    )
    (net (code "27") (name "Net-(ACCEL1-Pad1)") (class "Default")
      (node (ref "ACCEL1") (pin "1") (pinfunction "1_1") (pintype "passive"))
      (node (ref "J7") (pin "15") (pinfunction "15_15") (pintype "passive"))
    )
    (net (code "28") (name "Net-(ACCEL2-Pad1)") (class "Default")
      (node (ref "ACCEL2") (pin "1") (pinfunction "1_1") (pintype "passive"))
      (node (ref "J7") (pin "16") (pinfunction "16_16") (pintype "passive"))
    )
    (net (code "29") (name "Net-(BRAKE1-Pad1)") (class "Default")
      (node (ref "BRAKE1") (pin "1") (pinfunction "1_1") (pintype "passive"))
      (node (ref "J7") (pin "18") (pinfunction "18_18") (pintype "passive"))
    )
    (net (code "30") (name "Net-(BRAKE2-Pad1)") (class "Default")
      (node (ref "BRAKE2") (pin "1") (pinfunction "1_1") (pintype "passive"))
      (node (ref "J7") (pin "17") (pinfunction "17_17") (pintype "passive"))
    )
    (net (code "31") (name "Net-(D2-A)") (class "Default")
      (node (ref "D2") (pin "1") (pinfunction "A_1") (pintype "passive"))
      (node (ref "Q2") (pin "1") (pinfunction "G_1") (pintype "passive"))
      (node (ref "R6") (pin "2") (pinfunction "2_2") (pintype "passive"))
      (node (ref "R7") (pin "1") (pinfunction "1_1") (pintype "passive"))
    )
    (net (code "32") (name "Net-(D4-A)") (class "Default")
      (node (ref "D4") (pin "1") (pinfunction "A_1") (pintype "passive"))
      (node (ref "Q4") (pin "1") (pinfunction "G_1") (pintype "passive"))
      (node (ref "R10") (pin "1") (pinfunction "1_1") (pintype "passive"))
      (node (ref "R9") (pin "2") (pinfunction "2_2") (pintype "passive"))
    )
    (net (code "33") (name "Net-(D5-A)") (class "Default")
      (node (ref "D5") (pin "1") (pinfunction "A_1") (pintype "passive"))
      (node (ref "Q5") (pin "3") (pinfunction "D_3") (pintype "passive"))
      (node (ref "Q6") (pin "1") (pinfunction "G_1") (pintype "passive"))
      (node (ref "R11") (pin "1") (pinfunction "1_1") (pintype "passive"))
    )
    (net (code "34") (name "Net-(Q1-D)") (class "Default")
      (node (ref "Q1") (pin "3") (pinfunction "D_3") (pintype "passive"))
      (node (ref "R6") (pin "1") (pinfunction "1_1") (pintype "passive"))
    )
    (net (code "35") (name "Net-(Q3-D)") (class "Default")
      (node (ref "Q3") (pin "3") (pinfunction "D_3") (pintype "passive"))
      (node (ref "R9") (pin "1") (pinfunction "1_1") (pintype "passive"))
    )
    (net (code "36") (name "OKHS_IN") (class "Default")
      (node (ref "J1") (pin "13") (pinfunction "13_13") (pintype "passive"))
      (node (ref "J7") (pin "9") (pinfunction "9_9") (pintype "passive"))
    )
    (net (code "37") (name "REFERENCE_EXT") (class "Default")
      (node (ref "J1") (pin "11") (pinfunction "11_11") (pintype "passive"))
      (node (ref "J7") (pin "12") (pinfunction "12_12") (pintype "passive"))
    )
    (net (code "38") (name "SHDN_A") (class "Default")
      (node (ref "J5") (pin "1") (pinfunction "1_1") (pintype "passive"))
      (node (ref "J5") (pin "2") (pinfunction "2_2") (pintype "passive"))
      (node (ref "XF1") (pin "3") (pinfunction "2_3") (pintype "passive"))
      (node (ref "XF1") (pin "4") (pinfunction "2_4") (pintype "passive"))
    )
    (net (code "39") (name "SHDN_B") (class "Default")
      (node (ref "J12") (pin "5") (pinfunction "5_5") (pintype "passive"))
      (node (ref "J5") (pin "3") (pinfunction "3_3") (pintype "passive"))
      (node (ref "J5") (pin "4") (pinfunction "4_4") (pintype "passive"))
      (node (ref "J7") (pin "23") (pinfunction "23_23") (pintype "passive"))
      (node (ref "J7") (pin "24") (pinfunction "24_24") (pintype "passive"))
    )
    (net (code "40") (name "SHDN_G") (class "Default")
      (node (ref "J2") (pin "5") (pinfunction "5_5") (pintype "passive"))
      (node (ref "J7") (pin "1") (pinfunction "1_1") (pintype "passive"))
      (node (ref "J7") (pin "2") (pinfunction "2_2") (pintype "passive"))
    )
    (net (code "41") (name "SHDN_H") (class "Default")
      (node (ref "J2") (pin "6") (pinfunction "6_6") (pintype "passive"))
      (node (ref "J3") (pin "8") (pinfunction "8_8") (pintype "passive"))
    )
    (net (code "42") (name "SHDN_I") (class "Default")
      (node (ref "J3") (pin "6") (pinfunction "6_6") (pintype "passive"))
      (node (ref "J8") (pin "1") (pinfunction "1_1") (pintype "passive"))
      (node (ref "J8") (pin "2") (pinfunction "2_2") (pintype "passive"))
    )
    (net (code "43") (name "SHDN_J") (class "Default")
      (node (ref "J12") (pin "2") (pinfunction "2_2") (pintype "passive"))
      (node (ref "J7") (pin "5") (pinfunction "5_5") (pintype "passive"))
      (node (ref "J8") (pin "3") (pinfunction "3_3") (pintype "passive"))
      (node (ref "J8") (pin "4") (pinfunction "4_4") (pintype "passive"))
      (node (ref "J9") (pin "1") (pinfunction "1_1") (pintype "passive"))
      (node (ref "J9") (pin "2") (pinfunction "2_2") (pintype "passive"))
    )
    (net (code "44") (name "SHDN_K") (class "Default")
      (node (ref "J1") (pin "7") (pinfunction "7_7") (pintype "passive"))
      (node (ref "J1") (pin "8") (pinfunction "8_8") (pintype "passive"))
      (node (ref "J12") (pin "6") (pinfunction "6_6") (pintype "passive"))
      (node (ref "J9") (pin "3") (pinfunction "3_3") (pintype "passive"))
      (node (ref "J9") (pin "4") (pinfunction "4_4") (pintype "passive"))
    )
    (net (code "45") (name "STEERING_1_EXT") (class "Default")
      (node (ref "J14") (pin "7") (pinfunction "7_7") (pintype "passive"))
      (node (ref "J7") (pin "19") (pinfunction "19_19") (pintype "passive"))
    )
    (net (code "46") (name "STEERING_2_EXT") (class "Default")
      (node (ref "J14") (pin "6") (pinfunction "6_6") (pintype "passive"))
      (node (ref "J7") (pin "20") (pinfunction "20_20") (pintype "passive"))
    )
    (net (code "47") (name "STEERING_RX_N") (class "Default")
      (node (ref "J14") (pin "5") (pinfunction "5_5") (pintype "passive"))
      (node (ref "J6") (pin "14") (pinfunction "14_14") (pintype "passive"))
    )
    (net (code "48") (name "STEERING_RX_P") (class "Default")
      (node (ref "J14") (pin "2") (pinfunction "2_2") (pintype "passive"))
      (node (ref "J6") (pin "13") (pinfunction "13_13") (pintype "passive"))
    )
    (net (code "49") (name "STEERING_TX_N") (class "Default")
      (node (ref "J14") (pin "4") (pinfunction "4_4") (pintype "passive"))
      (node (ref "J6") (pin "10") (pinfunction "10_10") (pintype "passive"))
    )
    (net (code "50") (name "STEERING_TX_P") (class "Default")
      (node (ref "J14") (pin "3") (pinfunction "3_3") (pintype "passive"))
      (node (ref "J6") (pin "9") (pinfunction "9_9") (pintype "passive"))
    )
    (net (code "51") (name "THERM_FL_EXT") (class "Default")
      (node (ref "J13") (pin "2") (pinfunction "2_2") (pintype "passive"))
      (node (ref "J7") (pin "3") (pinfunction "3_3") (pintype "passive"))
    )
    (net (code "52") (name "THERM_FR_EXT") (class "Default")
      (node (ref "J4") (pin "2") (pinfunction "2_2") (pintype "passive"))
      (node (ref "J7") (pin "4") (pinfunction "4_4") (pintype "passive"))
    )
    (net (code "53") (name "unconnected-(J2-Pad8)") (class "Default")
      (node (ref "J2") (pin "8") (pinfunction "8_8") (pintype "passive"))
    )
    (net (code "54") (name "unconnected-(J3-Pad5)") (class "Default")
      (node (ref "J3") (pin "5") (pinfunction "5_5") (pintype "passive"))
    )
    (net (code "55") (name "unconnected-(J7-Pad21)") (class "Default")
      (node (ref "J7") (pin "21") (pinfunction "21_21") (pintype "passive"))
    )
    (net (code "56") (name "unconnected-(J7-Pad22)") (class "Default")
      (node (ref "J7") (pin "22") (pinfunction "22_22") (pintype "passive"))
    )
    (net (code "57") (name "unconnected-(J12-Pad7)") (class "Default")
      (node (ref "J12") (pin "7") (pinfunction "7_7") (pintype "passive"))
    )
  )
)
